# JugendNetzteil.net
KiCad netlist of a schematic drawn in EAGLE
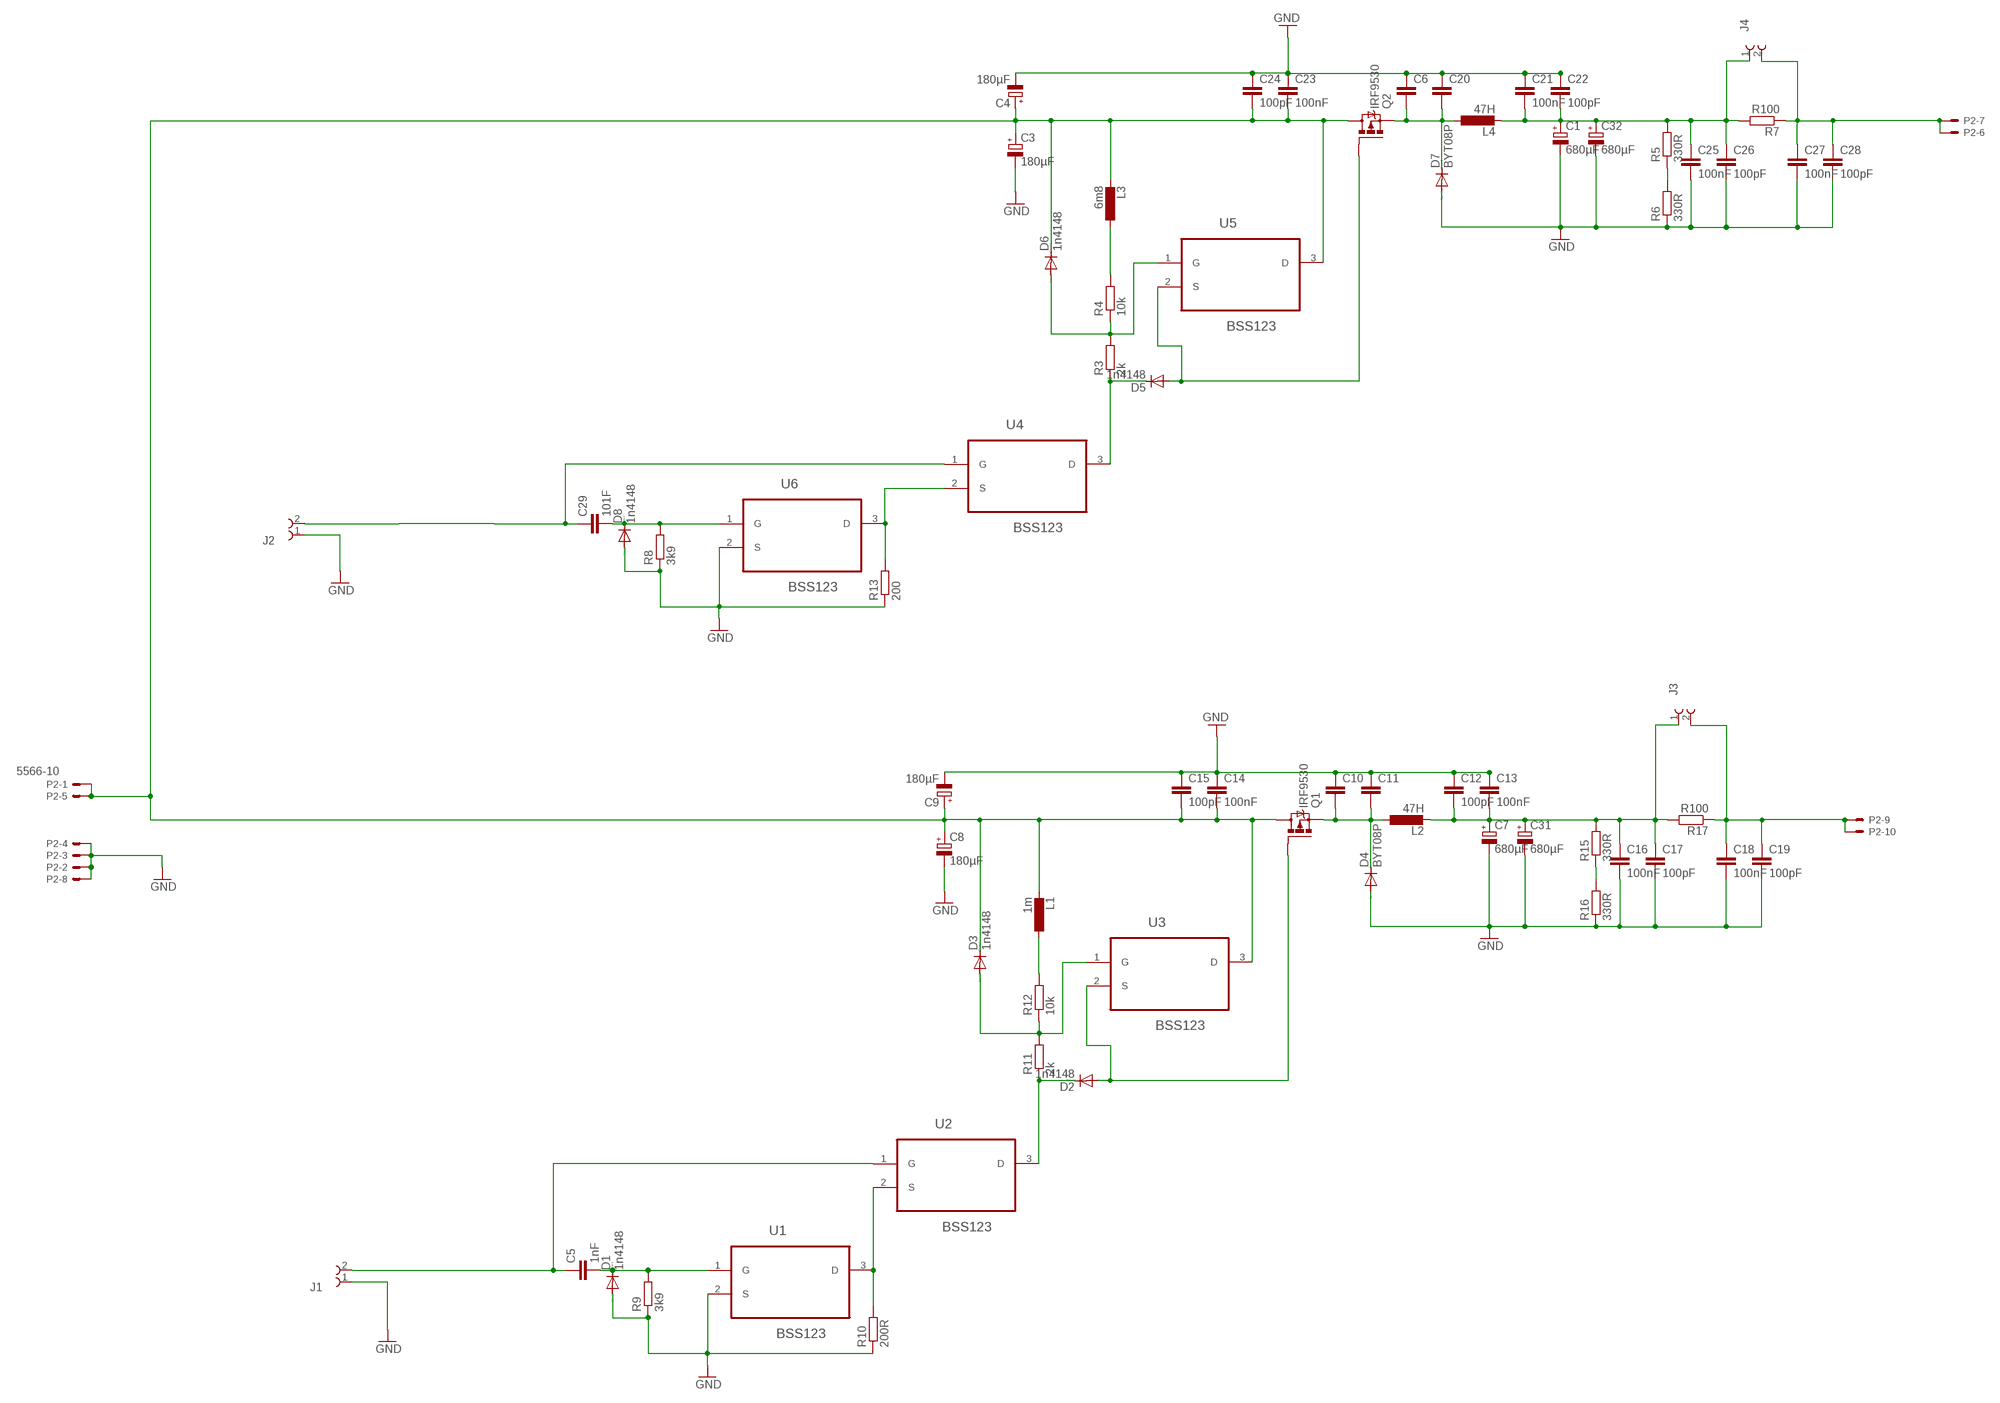
[diagram p0: schematic, sheet 1]

(export (version "E")
  (design (tool "Eeschema 10.0.6"))
  (components
    (comp (ref "C1")
      (value "680µF")
      (footprint "eagle-import:TT5D11")
      (libsource (lib "eagle-import") (part "CPOL-EUTT5D11"))
    )
    (comp (ref "C3")
      (value "180µF")
      (footprint "eagle-import:E5-8,5")
      (libsource (lib "eagle-import") (part "CPOL-EUE5-8.5"))
    )
    (comp (ref "C4")
      (value "180µF")
      (footprint "eagle-import:E5-8,5")
      (libsource (lib "eagle-import") (part "CPOL-EUE5-8.5"))
    )
    (comp (ref "C5")
      (value "1nF")
      (footprint "eagle-import:C0805")
      (libsource (lib "eagle-import") (part "resistor_348_C-EUC0805"))
    )
    (comp (ref "C6")
      (value "C-EUC1206")
      (footprint "eagle-import:C1206")
      (libsource (lib "eagle-import") (part "C-EUC1206"))
    )
    (comp (ref "C7")
      (value "680µF")
      (footprint "eagle-import:TT5D11")
      (libsource (lib "eagle-import") (part "CPOL-EUTT5D11"))
    )
    (comp (ref "C8")
      (value "180µF")
      (footprint "eagle-import:E5-8,5")
      (libsource (lib "eagle-import") (part "CPOL-EUE5-8.5"))
    )
    (comp (ref "C9")
      (value "180µF")
      (footprint "eagle-import:E5-8,5")
      (libsource (lib "eagle-import") (part "CPOL-EUE5-8.5"))
    )
    (comp (ref "C10")
      (value "C-EUC1206")
      (footprint "eagle-import:C1206")
      (libsource (lib "eagle-import") (part "C-EUC1206"))
    )
    (comp (ref "C11")
      (value "C-EUC1206")
      (footprint "eagle-import:C1206")
      (libsource (lib "eagle-import") (part "C-EUC1206"))
    )
    (comp (ref "C12")
      (value "100pF")
      (footprint "eagle-import:C1206")
      (libsource (lib "eagle-import") (part "C-EUC1206"))
    )
    (comp (ref "C13")
      (value "100nF")
      (footprint "eagle-import:C1206")
      (libsource (lib "eagle-import") (part "C-EUC1206"))
    )
    (comp (ref "C14")
      (value "100nF")
      (footprint "eagle-import:C1206")
      (libsource (lib "eagle-import") (part "C-EUC1206"))
    )
    (comp (ref "C15")
      (value "100pF")
      (footprint "eagle-import:C1206")
      (libsource (lib "eagle-import") (part "C-EUC1206"))
    )
    (comp (ref "C16")
      (value "100nF")
      (footprint "eagle-import:C1206")
      (libsource (lib "eagle-import") (part "C-EUC1206"))
    )
    (comp (ref "C17")
      (value "100pF")
      (footprint "eagle-import:C1206")
      (libsource (lib "eagle-import") (part "C-EUC1206"))
    )
    (comp (ref "C18")
      (value "100nF")
      (footprint "eagle-import:C1206")
      (libsource (lib "eagle-import") (part "C-EUC1206"))
    )
    (comp (ref "C19")
      (value "100pF")
      (footprint "eagle-import:C1206")
      (libsource (lib "eagle-import") (part "C-EUC1206"))
    )
    (comp (ref "C20")
      (value "C-EUC1206")
      (footprint "eagle-import:C1206")
      (libsource (lib "eagle-import") (part "C-EUC1206"))
    )
    (comp (ref "C21")
      (value "100nF")
      (footprint "eagle-import:C1206")
      (libsource (lib "eagle-import") (part "C-EUC1206"))
    )
    (comp (ref "C22")
      (value "100pF")
      (footprint "eagle-import:C1206")
      (libsource (lib "eagle-import") (part "C-EUC1206"))
    )
    (comp (ref "C23")
      (value "100nF")
      (footprint "eagle-import:C1206")
      (libsource (lib "eagle-import") (part "C-EUC1206"))
    )
    (comp (ref "C24")
      (value "100pF")
      (footprint "eagle-import:C1206")
      (libsource (lib "eagle-import") (part "C-EUC1206"))
    )
    (comp (ref "C25")
      (value "100nF")
      (footprint "eagle-import:C1206")
      (libsource (lib "eagle-import") (part "C-EUC1206"))
    )
    (comp (ref "C26")
      (value "100pF")
      (footprint "eagle-import:C1206")
      (libsource (lib "eagle-import") (part "C-EUC1206"))
    )
    (comp (ref "C27")
      (value "100nF")
      (footprint "eagle-import:C1206")
      (libsource (lib "eagle-import") (part "C-EUC1206"))
    )
    (comp (ref "C28")
      (value "100pF")
      (footprint "eagle-import:C1206")
      (libsource (lib "eagle-import") (part "C-EUC1206"))
    )
    (comp (ref "C29")
      (value "101F")
      (footprint "eagle-import:C0805")
      (libsource (lib "eagle-import") (part "resistor_348_C-EUC0805"))
    )
    (comp (ref "C31")
      (value "680µF")
      (footprint "eagle-import:TT5D11")
      (libsource (lib "eagle-import") (part "CPOL-EUTT5D11"))
    )
    (comp (ref "C32")
      (value "680µF")
      (footprint "eagle-import:TT5D11")
      (libsource (lib "eagle-import") (part "CPOL-EUTT5D11"))
    )
    (comp (ref "D1")
      (value "1n4148")
      (footprint "eagle-import:MINIMELF")
      (libsource (lib "eagle-import") (part "DIODE-MINIMELF"))
    )
    (comp (ref "D2")
      (value "1n4148")
      (footprint "eagle-import:MINIMELF")
      (libsource (lib "eagle-import") (part "DIODE-MINIMELF"))
    )
    (comp (ref "D3")
      (value "1n4148")
      (footprint "eagle-import:MINIMELF")
      (libsource (lib "eagle-import") (part "DIODE-MINIMELF"))
    )
    (comp (ref "D4")
      (value "BYT08P")
      (footprint "eagle-import:TO220ACS")
      (libsource (lib "eagle-import") (part "BYT08P"))
    )
    (comp (ref "D5")
      (value "1n4148")
      (footprint "eagle-import:MINIMELF")
      (libsource (lib "eagle-import") (part "DIODE-MINIMELF"))
    )
    (comp (ref "D6")
      (value "1n4148")
      (footprint "eagle-import:MINIMELF")
      (libsource (lib "eagle-import") (part "DIODE-MINIMELF"))
    )
    (comp (ref "D7")
      (value "BYT08P")
      (footprint "eagle-import:TO220ACS")
      (libsource (lib "eagle-import") (part "BYT08P"))
    )
    (comp (ref "D8")
      (value "1n4148")
      (footprint "eagle-import:MINIMELF")
      (libsource (lib "eagle-import") (part "DIODE-MINIMELF"))
    )
    (comp (ref "J1")
      (value "691210910002")
      (footprint "eagle-import:691210910002")
      (libsource (lib "eagle-import") (part "691210910002"))
    )
    (comp (ref "J2")
      (value "691210910002")
      (footprint "eagle-import:691210910002")
      (libsource (lib "eagle-import") (part "691210910002"))
    )
    (comp (ref "J3")
      (value "691210910002")
      (footprint "eagle-import:691210910002")
      (libsource (lib "eagle-import") (part "691210910002"))
    )
    (comp (ref "J4")
      (value "691210910002")
      (footprint "eagle-import:691210910002")
      (libsource (lib "eagle-import") (part "691210910002"))
    )
    (comp (ref "L1")
      (value "1m")
      (footprint "eagle-import:0207_15")
      (libsource (lib "eagle-import") (part "L-EU0207/15"))
    )
    (comp (ref "L2")
      (value "47H")
      (footprint "eagle-import:TJ8-U1")
      (libsource (lib "eagle-import") (part "L-EUTJ8-U1"))
    )
    (comp (ref "L3")
      (value "6m8")
      (footprint "eagle-import:0207_15")
      (libsource (lib "eagle-import") (part "L-EU0207/15"))
    )
    (comp (ref "L4")
      (value "47H")
      (footprint "eagle-import:TJ8-U1")
      (libsource (lib "eagle-import") (part "L-EUTJ8-U1"))
    )
    (comp (ref "P2")
      (value "5566-10")
      (footprint "eagle-import:5566-10")
      (libsource (lib "eagle-import") (part "5566-10"))
    )
    (comp (ref "Q1")
      (value "IRF9530")
      (footprint "eagle-import:TO220BV")
      (libsource (lib "eagle-import") (part "IRF9530"))
    )
    (comp (ref "Q2")
      (value "IRF9530")
      (footprint "eagle-import:TO220BV")
      (libsource (lib "eagle-import") (part "IRF9530"))
    )
    (comp (ref "R3")
      (value "2k")
      (footprint "eagle-import:R0805")
      (libsource (lib "eagle-import") (part "resistor_348_R-EU_R0805"))
    )
    (comp (ref "R4")
      (value "10k")
      (footprint "eagle-import:R0805")
      (libsource (lib "eagle-import") (part "resistor_348_R-EU_R0805"))
    )
    (comp (ref "R5")
      (value "330R")
      (footprint "eagle-import:P0817V")
      (libsource (lib "eagle-import") (part "R-EU_0817/7V"))
    )
    (comp (ref "R6")
      (value "330R")
      (footprint "eagle-import:P0817V")
      (libsource (lib "eagle-import") (part "R-EU_0817/7V"))
    )
    (comp (ref "R7")
      (value "R100")
      (footprint "eagle-import:P0817V")
      (libsource (lib "eagle-import") (part "R-EU_0817/7V"))
    )
    (comp (ref "R8")
      (value "3k9")
      (footprint "eagle-import:R0805")
      (libsource (lib "eagle-import") (part "resistor_348_R-EU_R0805"))
    )
    (comp (ref "R9")
      (value "3k9")
      (footprint "eagle-import:R0805")
      (libsource (lib "eagle-import") (part "resistor_348_R-EU_R0805"))
    )
    (comp (ref "R10")
      (value "200R")
      (footprint "eagle-import:R0805")
      (libsource (lib "eagle-import") (part "resistor_348_R-EU_R0805"))
    )
    (comp (ref "R11")
      (value "2k")
      (footprint "eagle-import:R0805")
      (libsource (lib "eagle-import") (part "resistor_348_R-EU_R0805"))
    )
    (comp (ref "R12")
      (value "10k")
      (footprint "eagle-import:R0805")
      (libsource (lib "eagle-import") (part "resistor_348_R-EU_R0805"))
    )
    (comp (ref "R13")
      (value "200")
      (footprint "eagle-import:R0805")
      (libsource (lib "eagle-import") (part "resistor_348_R-EU_R0805"))
    )
    (comp (ref "R15")
      (value "330R")
      (footprint "eagle-import:P0817V")
      (libsource (lib "eagle-import") (part "R-EU_0817/7V"))
    )
    (comp (ref "R16")
      (value "330R")
      (footprint "eagle-import:P0817V")
      (libsource (lib "eagle-import") (part "R-EU_0817/7V"))
    )
    (comp (ref "R17")
      (value "R100")
      (footprint "eagle-import:P0817V")
      (libsource (lib "eagle-import") (part "R-EU_0817/7V"))
    )
    (comp (ref "U1")
      (value "BSS123")
      (footprint "eagle-import:SOT95P280X130-3N")
      (fields (field (name "MPN") "TSM2314CX"))
      (libsource (lib "eagle-import") (part "TSM2314CX"))
    )
    (comp (ref "U2")
      (value "BSS123")
      (footprint "eagle-import:SOT95P280X130-3N")
      (fields (field (name "MPN") "TSM2314CX"))
      (libsource (lib "eagle-import") (part "TSM2314CX"))
    )
    (comp (ref "U3")
      (value "BSS123")
      (footprint "eagle-import:SOT95P280X130-3N")
      (fields (field (name "MPN") "TSM2314CX"))
      (libsource (lib "eagle-import") (part "TSM2314CX"))
    )
    (comp (ref "U4")
      (value "BSS123")
      (footprint "eagle-import:SOT95P280X130-3N")
      (fields (field (name "MPN") "TSM2314CX"))
      (libsource (lib "eagle-import") (part "TSM2314CX"))
    )
    (comp (ref "U5")
      (value "BSS123")
      (footprint "eagle-import:SOT95P280X130-3N")
      (fields (field (name "MPN") "TSM2314CX"))
      (libsource (lib "eagle-import") (part "TSM2314CX"))
    )
    (comp (ref "U6")
      (value "BSS123")
      (footprint "eagle-import:SOT95P280X130-3N")
      (fields (field (name "MPN") "TSM2314CX"))
      (libsource (lib "eagle-import") (part "TSM2314CX"))
    )
  )
  (nets
    (net (code "1") (name "GND") (class "Default")
      (node (ref "C1") (pin "-") (pinfunction "-_-") (pintype "passive"))
      (node (ref "C10") (pin "1") (pinfunction "1_1") (pintype "passive"))
      (node (ref "C11") (pin "1") (pinfunction "1_1") (pintype "passive"))
      (node (ref "C12") (pin "1") (pinfunction "1_1") (pintype "passive"))
      (node (ref "C13") (pin "1") (pinfunction "1_1") (pintype "passive"))
      (node (ref "C14") (pin "1") (pinfunction "1_1") (pintype "passive"))
      (node (ref "C15") (pin "1") (pinfunction "1_1") (pintype "passive"))
      (node (ref "C16") (pin "2") (pinfunction "2_2") (pintype "passive"))
      (node (ref "C17") (pin "2") (pinfunction "2_2") (pintype "passive"))
      (node (ref "C18") (pin "2") (pinfunction "2_2") (pintype "passive"))
      (node (ref "C19") (pin "2") (pinfunction "2_2") (pintype "passive"))
      (node (ref "C20") (pin "1") (pinfunction "1_1") (pintype "passive"))
      (node (ref "C21") (pin "1") (pinfunction "1_1") (pintype "passive"))
      (node (ref "C22") (pin "1") (pinfunction "1_1") (pintype "passive"))
      (node (ref "C23") (pin "1") (pinfunction "1_1") (pintype "passive"))
      (node (ref "C24") (pin "1") (pinfunction "1_1") (pintype "passive"))
      (node (ref "C25") (pin "2") (pinfunction "2_2") (pintype "passive"))
      (node (ref "C26") (pin "2") (pinfunction "2_2") (pintype "passive"))
      (node (ref "C27") (pin "2") (pinfunction "2_2") (pintype "passive"))
      (node (ref "C28") (pin "2") (pinfunction "2_2") (pintype "passive"))
      (node (ref "C3") (pin "-") (pinfunction "-_-") (pintype "passive"))
      (node (ref "C31") (pin "-") (pinfunction "-_-") (pintype "passive"))
      (node (ref "C32") (pin "-") (pinfunction "-_-") (pintype "passive"))
      (node (ref "C4") (pin "-") (pinfunction "-_-") (pintype "passive"))
      (node (ref "C6") (pin "1") (pinfunction "1_1") (pintype "passive"))
      (node (ref "C7") (pin "-") (pinfunction "-_-") (pintype "passive"))
      (node (ref "C8") (pin "-") (pinfunction "-_-") (pintype "passive"))
      (node (ref "C9") (pin "-") (pinfunction "-_-") (pintype "passive"))
      (node (ref "D1") (pin "A") (pinfunction "A_A") (pintype "passive"))
      (node (ref "D4") (pin "A") (pinfunction "A_A") (pintype "passive"))
      (node (ref "D7") (pin "A") (pinfunction "A_A") (pintype "passive"))
      (node (ref "D8") (pin "A") (pinfunction "A_A") (pintype "passive"))
      (node (ref "J1") (pin "1") (pinfunction "1_1") (pintype "passive"))
      (node (ref "J2") (pin "1") (pinfunction "1_1") (pintype "passive"))
      (node (ref "P2") (pin "2") (pinfunction "S_2") (pintype "passive"))
      (node (ref "P2") (pin "3") (pinfunction "S_3") (pintype "passive"))
      (node (ref "P2") (pin "4") (pinfunction "S_4") (pintype "passive"))
      (node (ref "P2") (pin "8") (pinfunction "S_8") (pintype "passive"))
      (node (ref "R10") (pin "1") (pinfunction "1_1") (pintype "passive"))
      (node (ref "R13") (pin "1") (pinfunction "1_1") (pintype "passive"))
      (node (ref "R16") (pin "1") (pinfunction "1_1") (pintype "passive"))
      (node (ref "R6") (pin "1") (pinfunction "1_1") (pintype "passive"))
      (node (ref "R8") (pin "1") (pinfunction "1_1") (pintype "passive"))
      (node (ref "R9") (pin "1") (pinfunction "1_1") (pintype "passive"))
      (node (ref "U1") (pin "2") (pinfunction "S_2") (pintype "passive"))
      (node (ref "U6") (pin "2") (pinfunction "S_2") (pintype "passive"))
    )
    (net (code "2") (name "Net-(C1-Pad+)") (class "Default")
      (node (ref "C1") (pin "+") (pinfunction "+_+") (pintype "passive"))
      (node (ref "C21") (pin "2") (pinfunction "2_2") (pintype "passive"))
      (node (ref "C22") (pin "2") (pinfunction "2_2") (pintype "passive"))
      (node (ref "C25") (pin "1") (pinfunction "1_1") (pintype "passive"))
      (node (ref "C26") (pin "1") (pinfunction "1_1") (pintype "passive"))
      (node (ref "C32") (pin "+") (pinfunction "+_+") (pintype "passive"))
      (node (ref "J4") (pin "1") (pinfunction "1_1") (pintype "passive"))
      (node (ref "L4") (pin "2") (pinfunction "2_2") (pintype "passive"))
      (node (ref "R5") (pin "2") (pinfunction "2_2") (pintype "passive"))
      (node (ref "R7") (pin "2") (pinfunction "2_2") (pintype "passive"))
    )
    (net (code "3") (name "Net-(C10-Pad2)") (class "Default")
      (node (ref "C10") (pin "2") (pinfunction "2_2") (pintype "passive"))
      (node (ref "C11") (pin "2") (pinfunction "2_2") (pintype "passive"))
      (node (ref "D4") (pin "C") (pinfunction "C_C") (pintype "passive"))
      (node (ref "L2") (pin "1") (pinfunction "1_1") (pintype "passive"))
      (node (ref "Q1") (pin "S") (pinfunction "S_S") (pintype "passive"))
    )
    (net (code "4") (name "Net-(C12-Pad2)") (class "Default")
      (node (ref "C12") (pin "2") (pinfunction "2_2") (pintype "passive"))
      (node (ref "C13") (pin "2") (pinfunction "2_2") (pintype "passive"))
      (node (ref "C16") (pin "1") (pinfunction "1_1") (pintype "passive"))
      (node (ref "C17") (pin "1") (pinfunction "1_1") (pintype "passive"))
      (node (ref "C31") (pin "+") (pinfunction "+_+") (pintype "passive"))
      (node (ref "C7") (pin "+") (pinfunction "+_+") (pintype "passive"))
      (node (ref "J3") (pin "1") (pinfunction "1_1") (pintype "passive"))
      (node (ref "L2") (pin "2") (pinfunction "2_2") (pintype "passive"))
      (node (ref "R15") (pin "2") (pinfunction "2_2") (pintype "passive"))
      (node (ref "R17") (pin "2") (pinfunction "2_2") (pintype "passive"))
    )
    (net (code "5") (name "Net-(C20-Pad2)") (class "Default")
      (node (ref "C20") (pin "2") (pinfunction "2_2") (pintype "passive"))
      (node (ref "C6") (pin "2") (pinfunction "2_2") (pintype "passive"))
      (node (ref "D7") (pin "C") (pinfunction "C_C") (pintype "passive"))
      (node (ref "L4") (pin "1") (pinfunction "1_1") (pintype "passive"))
      (node (ref "Q2") (pin "S") (pinfunction "S_S") (pintype "passive"))
    )
    (net (code "6") (name "Net-(L1-Pad1)") (class "Default")
      (node (ref "L1") (pin "1") (pinfunction "1_1") (pintype "passive"))
      (node (ref "R12") (pin "2") (pinfunction "2_2") (pintype "passive"))
    )
    (net (code "7") (name "Net-(L3-Pad1)") (class "Default")
      (node (ref "L3") (pin "1") (pinfunction "1_1") (pintype "passive"))
      (node (ref "R4") (pin "2") (pinfunction "2_2") (pintype "passive"))
    )
    (net (code "8") (name "Net-(P2A-S)") (class "Default")
      (node (ref "C14") (pin "2") (pinfunction "2_2") (pintype "passive"))
      (node (ref "C15") (pin "2") (pinfunction "2_2") (pintype "passive"))
      (node (ref "C23") (pin "2") (pinfunction "2_2") (pintype "passive"))
      (node (ref "C24") (pin "2") (pinfunction "2_2") (pintype "passive"))
      (node (ref "C3") (pin "+") (pinfunction "+_+") (pintype "passive"))
      (node (ref "C4") (pin "+") (pinfunction "+_+") (pintype "passive"))
      (node (ref "C8") (pin "+") (pinfunction "+_+") (pintype "passive"))
      (node (ref "C9") (pin "+") (pinfunction "+_+") (pintype "passive"))
      (node (ref "D3") (pin "C") (pinfunction "C_C") (pintype "passive"))
      (node (ref "D6") (pin "C") (pinfunction "C_C") (pintype "passive"))
      (node (ref "L1") (pin "2") (pinfunction "2_2") (pintype "passive"))
      (node (ref "L3") (pin "2") (pinfunction "2_2") (pintype "passive"))
      (node (ref "P2") (pin "1") (pinfunction "S_1") (pintype "passive"))
      (node (ref "P2") (pin "5") (pinfunction "S_5") (pintype "passive"))
      (node (ref "Q1") (pin "D") (pinfunction "D_D") (pintype "passive"))
      (node (ref "Q2") (pin "D") (pinfunction "D_D") (pintype "passive"))
      (node (ref "U3") (pin "3") (pinfunction "D_3") (pintype "output"))
      (node (ref "U5") (pin "3") (pinfunction "D_3") (pintype "output"))
    )
    (net (code "9") (name "Net-(P2B-S)") (class "Default")
      (node (ref "C18") (pin "1") (pinfunction "1_1") (pintype "passive"))
      (node (ref "C19") (pin "1") (pinfunction "1_1") (pintype "passive"))
      (node (ref "J3") (pin "2") (pinfunction "2_2") (pintype "passive"))
      (node (ref "P2") (pin "10") (pinfunction "S_10") (pintype "passive"))
      (node (ref "P2") (pin "9") (pinfunction "S_9") (pintype "passive"))
      (node (ref "R17") (pin "1") (pinfunction "1_1") (pintype "passive"))
    )
    (net (code "10") (name "Net-(P2G-S)") (class "Default")
      (node (ref "C27") (pin "1") (pinfunction "1_1") (pintype "passive"))
      (node (ref "C28") (pin "1") (pinfunction "1_1") (pintype "passive"))
      (node (ref "J4") (pin "2") (pinfunction "2_2") (pintype "passive"))
      (node (ref "P2") (pin "6") (pinfunction "S_6") (pintype "passive"))
      (node (ref "P2") (pin "7") (pinfunction "S_7") (pintype "passive"))
      (node (ref "R7") (pin "1") (pinfunction "1_1") (pintype "passive"))
    )
    (net (code "11") (name "Net-(R5-Pad1)") (class "Default")
      (node (ref "R5") (pin "1") (pinfunction "1_1") (pintype "passive"))
      (node (ref "R6") (pin "2") (pinfunction "2_2") (pintype "passive"))
    )
    (net (code "12") (name "Net-(R15-Pad1)") (class "Default")
      (node (ref "R15") (pin "1") (pinfunction "1_1") (pintype "passive"))
      (node (ref "R16") (pin "2") (pinfunction "2_2") (pintype "passive"))
    )
    (net (code "13") (name "Net-(U1-D)") (class "Default")
      (node (ref "R10") (pin "2") (pinfunction "2_2") (pintype "passive"))
      (node (ref "U1") (pin "3") (pinfunction "D_3") (pintype "output"))
      (node (ref "U2") (pin "2") (pinfunction "S_2") (pintype "passive"))
    )
    (net (code "14") (name "Net-(U1-G)") (class "Default")
      (node (ref "C5") (pin "2") (pinfunction "2_2") (pintype "passive"))
      (node (ref "D1") (pin "C") (pinfunction "C_C") (pintype "passive"))
      (node (ref "R9") (pin "2") (pinfunction "2_2") (pintype "passive"))
      (node (ref "U1") (pin "1") (pinfunction "G_1") (pintype "input"))
    )
    (net (code "15") (name "Net-(U2-D)") (class "Default")
      (node (ref "D2") (pin "C") (pinfunction "C_C") (pintype "passive"))
      (node (ref "R11") (pin "1") (pinfunction "1_1") (pintype "passive"))
      (node (ref "U2") (pin "3") (pinfunction "D_3") (pintype "output"))
    )
    (net (code "16") (name "Net-(U2-G)") (class "Default")
      (node (ref "C5") (pin "1") (pinfunction "1_1") (pintype "passive"))
      (node (ref "J1") (pin "2") (pinfunction "2_2") (pintype "passive"))
      (node (ref "U2") (pin "1") (pinfunction "G_1") (pintype "input"))
    )
    (net (code "17") (name "Net-(U3-G)") (class "Default")
      (node (ref "D3") (pin "A") (pinfunction "A_A") (pintype "passive"))
      (node (ref "R11") (pin "2") (pinfunction "2_2") (pintype "passive"))
      (node (ref "R12") (pin "1") (pinfunction "1_1") (pintype "passive"))
      (node (ref "U3") (pin "1") (pinfunction "G_1") (pintype "input"))
    )
    (net (code "18") (name "Net-(U3-S)") (class "Default")
      (node (ref "D2") (pin "A") (pinfunction "A_A") (pintype "passive"))
      (node (ref "Q1") (pin "G") (pinfunction "G_G") (pintype "passive"))
      (node (ref "U3") (pin "2") (pinfunction "S_2") (pintype "passive"))
    )
    (net (code "19") (name "Net-(U4-D)") (class "Default")
      (node (ref "D5") (pin "C") (pinfunction "C_C") (pintype "passive"))
      (node (ref "R3") (pin "1") (pinfunction "1_1") (pintype "passive"))
      (node (ref "U4") (pin "3") (pinfunction "D_3") (pintype "output"))
    )
    (net (code "20") (name "Net-(U4-G)") (class "Default")
      (node (ref "C29") (pin "1") (pinfunction "1_1") (pintype "passive"))
      (node (ref "J2") (pin "2") (pinfunction "2_2") (pintype "passive"))
      (node (ref "U4") (pin "1") (pinfunction "G_1") (pintype "input"))
    )
    (net (code "21") (name "Net-(U4-S)") (class "Default")
      (node (ref "R13") (pin "2") (pinfunction "2_2") (pintype "passive"))
      (node (ref "U4") (pin "2") (pinfunction "S_2") (pintype "passive"))
      (node (ref "U6") (pin "3") (pinfunction "D_3") (pintype "output"))
    )
    (net (code "22") (name "Net-(U5-G)") (class "Default")
      (node (ref "D6") (pin "A") (pinfunction "A_A") (pintype "passive"))
      (node (ref "R3") (pin "2") (pinfunction "2_2") (pintype "passive"))
      (node (ref "R4") (pin "1") (pinfunction "1_1") (pintype "passive"))
      (node (ref "U5") (pin "1") (pinfunction "G_1") (pintype "input"))
    )
    (net (code "23") (name "Net-(U5-S)") (class "Default")
      (node (ref "D5") (pin "A") (pinfunction "A_A") (pintype "passive"))
      (node (ref "Q2") (pin "G") (pinfunction "G_G") (pintype "passive"))
      (node (ref "U5") (pin "2") (pinfunction "S_2") (pintype "passive"))
    )
    (net (code "24") (name "Net-(U6-G)") (class "Default")
      (node (ref "C29") (pin "2") (pinfunction "2_2") (pintype "passive"))
      (node (ref "D8") (pin "C") (pinfunction "C_C") (pintype "passive"))
      (node (ref "R8") (pin "2") (pinfunction "2_2") (pintype "passive"))
      (node (ref "U6") (pin "1") (pinfunction "G_1") (pintype "input"))
    )
  )
)
